# 04_DDRAM.net
KiCad netlist of a schematic drawn in Altium Designer
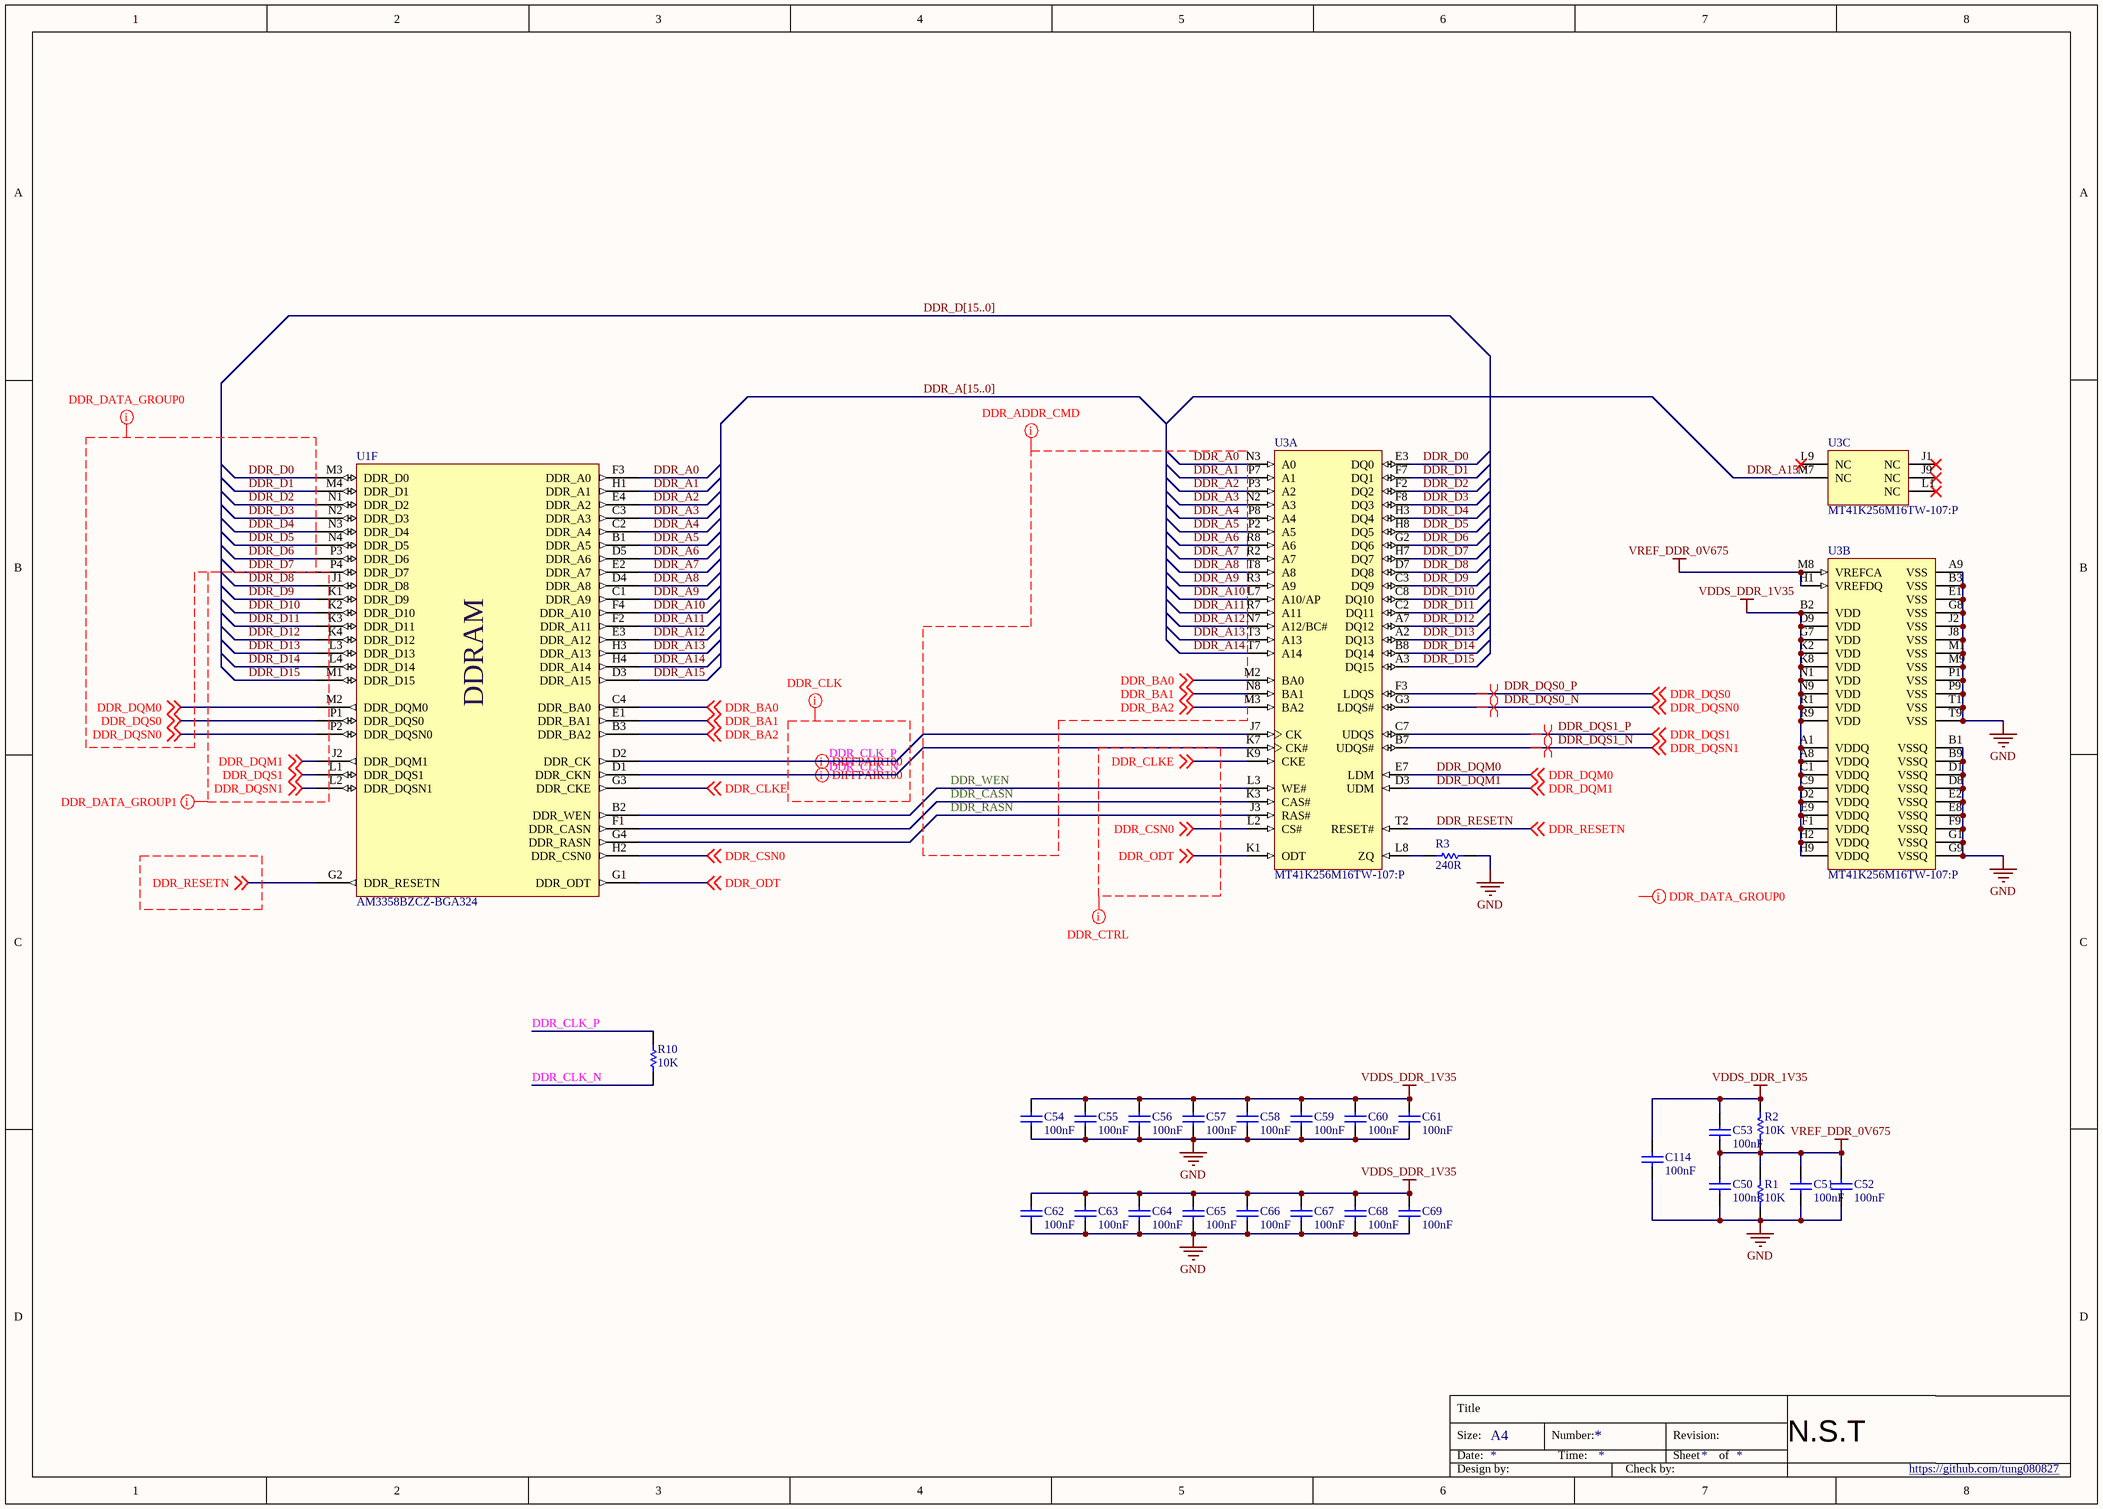
[diagram p0: 04. DDRAM.SchDoc]

(export (version "E")
  (design (tool "Eeschema 10.0.6"))
  (components
    (comp (ref "C50")
      (value "100nF")
      (footprint "CAPC1005X60X30LL05T10")
      (description "Chip Capacitor, 0.1 uF, +/- 10%, 16 V, -55 to 125 degC, 0402 (1005 Metric), RoHS, Tape and Reel")
      (fields (field (name "VOLTAGE") "16V") (field (name "TOLERANCE") "10%"))
      (libsource (lib "AM3358_DEV_BOARD") (part "CAP-NP-2"))
    )
    (comp (ref "C51")
      (value "100nF")
      (footprint "CAPC1005X60X30LL05T10")
      (description "Chip Capacitor, 0.1 uF, +/- 10%, 16 V, -55 to 125 degC, 0402 (1005 Metric), RoHS, Tape and Reel")
      (fields (field (name "VOLTAGE") "16V") (field (name "TOLERANCE") "10%"))
      (libsource (lib "AM3358_DEV_BOARD") (part "CAP-NP-2"))
    )
    (comp (ref "C52")
      (value "100nF")
      (footprint "CAPC1005X60X30LL05T10")
      (description "Chip Capacitor, 0.1 uF, +/- 10%, 16 V, -55 to 125 degC, 0402 (1005 Metric), RoHS, Tape and Reel")
      (fields (field (name "VOLTAGE") "16V") (field (name "TOLERANCE") "10%"))
      (libsource (lib "AM3358_DEV_BOARD") (part "CAP-NP-2"))
    )
    (comp (ref "C53")
      (value "100nF")
      (footprint "CAPC1005X60X30LL05T10")
      (description "Chip Capacitor, 0.1 uF, +/- 10%, 16 V, -55 to 125 degC, 0402 (1005 Metric), RoHS, Tape and Reel")
      (fields (field (name "VOLTAGE") "16V") (field (name "TOLERANCE") "10%"))
      (libsource (lib "AM3358_DEV_BOARD") (part "CAP-NP-2"))
    )
    (comp (ref "C54")
      (value "100nF")
      (footprint "CAPC1005X60X30LL05T10")
      (description "Chip Capacitor, 0.1 uF, +/- 10%, 16 V, -55 to 125 degC, 0402 (1005 Metric), RoHS, Tape and Reel")
      (fields (field (name "VOLTAGE") "16V") (field (name "TOLERANCE") "10%"))
      (libsource (lib "AM3358_DEV_BOARD") (part "CAP-NP-2"))
    )
    (comp (ref "C55")
      (value "100nF")
      (footprint "CAPC1005X60X30LL05T10")
      (description "Chip Capacitor, 0.1 uF, +/- 10%, 16 V, -55 to 125 degC, 0402 (1005 Metric), RoHS, Tape and Reel")
      (fields (field (name "VOLTAGE") "16V") (field (name "TOLERANCE") "10%"))
      (libsource (lib "AM3358_DEV_BOARD") (part "CAP-NP-2"))
    )
    (comp (ref "C56")
      (value "100nF")
      (footprint "CAPC1005X60X30LL05T10")
      (description "Chip Capacitor, 0.1 uF, +/- 10%, 16 V, -55 to 125 degC, 0402 (1005 Metric), RoHS, Tape and Reel")
      (fields (field (name "VOLTAGE") "16V") (field (name "TOLERANCE") "10%"))
      (libsource (lib "AM3358_DEV_BOARD") (part "CAP-NP-2"))
    )
    (comp (ref "C57")
      (value "100nF")
      (footprint "CAPC1005X60X30LL05T10")
      (description "Chip Capacitor, 0.1 uF, +/- 10%, 16 V, -55 to 125 degC, 0402 (1005 Metric), RoHS, Tape and Reel")
      (fields (field (name "VOLTAGE") "16V") (field (name "TOLERANCE") "10%"))
      (libsource (lib "AM3358_DEV_BOARD") (part "CAP-NP-2"))
    )
    (comp (ref "C58")
      (value "100nF")
      (footprint "CAPC1005X60X30LL05T10")
      (description "Chip Capacitor, 0.1 uF, +/- 10%, 16 V, -55 to 125 degC, 0402 (1005 Metric), RoHS, Tape and Reel")
      (fields (field (name "VOLTAGE") "16V") (field (name "TOLERANCE") "10%"))
      (libsource (lib "AM3358_DEV_BOARD") (part "CAP-NP-2"))
    )
    (comp (ref "C59")
      (value "100nF")
      (footprint "CAPC1005X60X30LL05T10")
      (description "Chip Capacitor, 0.1 uF, +/- 10%, 16 V, -55 to 125 degC, 0402 (1005 Metric), RoHS, Tape and Reel")
      (fields (field (name "VOLTAGE") "16V") (field (name "TOLERANCE") "10%"))
      (libsource (lib "AM3358_DEV_BOARD") (part "CAP-NP-2"))
    )
    (comp (ref "C60")
      (value "100nF")
      (footprint "CAPC1005X60X30LL05T10")
      (description "Chip Capacitor, 0.1 uF, +/- 10%, 16 V, -55 to 125 degC, 0402 (1005 Metric), RoHS, Tape and Reel")
      (fields (field (name "VOLTAGE") "16V") (field (name "TOLERANCE") "10%"))
      (libsource (lib "AM3358_DEV_BOARD") (part "CAP-NP-2"))
    )
    (comp (ref "C61")
      (value "100nF")
      (footprint "CAPC1005X60X30LL05T10")
      (description "Chip Capacitor, 0.1 uF, +/- 10%, 16 V, -55 to 125 degC, 0402 (1005 Metric), RoHS, Tape and Reel")
      (fields (field (name "VOLTAGE") "16V") (field (name "TOLERANCE") "10%"))
      (libsource (lib "AM3358_DEV_BOARD") (part "CAP-NP-2"))
    )
    (comp (ref "C62")
      (value "100nF")
      (footprint "CAPC1005X60X30LL05T10")
      (description "Chip Capacitor, 0.1 uF, +/- 10%, 16 V, -55 to 125 degC, 0402 (1005 Metric), RoHS, Tape and Reel")
      (fields (field (name "VOLTAGE") "16V") (field (name "TOLERANCE") "10%"))
      (libsource (lib "AM3358_DEV_BOARD") (part "CAP-NP-2"))
    )
    (comp (ref "C63")
      (value "100nF")
      (footprint "CAPC1005X60X30LL05T10")
      (description "Chip Capacitor, 0.1 uF, +/- 10%, 16 V, -55 to 125 degC, 0402 (1005 Metric), RoHS, Tape and Reel")
      (fields (field (name "VOLTAGE") "16V") (field (name "TOLERANCE") "10%"))
      (libsource (lib "AM3358_DEV_BOARD") (part "CAP-NP-2"))
    )
    (comp (ref "C64")
      (value "100nF")
      (footprint "CAPC1005X60X30LL05T10")
      (description "Chip Capacitor, 0.1 uF, +/- 10%, 16 V, -55 to 125 degC, 0402 (1005 Metric), RoHS, Tape and Reel")
      (fields (field (name "VOLTAGE") "16V") (field (name "TOLERANCE") "10%"))
      (libsource (lib "AM3358_DEV_BOARD") (part "CAP-NP-2"))
    )
    (comp (ref "C65")
      (value "100nF")
      (footprint "CAPC1005X60X30LL05T10")
      (description "Chip Capacitor, 0.1 uF, +/- 10%, 16 V, -55 to 125 degC, 0402 (1005 Metric), RoHS, Tape and Reel")
      (fields (field (name "VOLTAGE") "16V") (field (name "TOLERANCE") "10%"))
      (libsource (lib "AM3358_DEV_BOARD") (part "CAP-NP-2"))
    )
    (comp (ref "C66")
      (value "100nF")
      (footprint "CAPC1005X60X30LL05T10")
      (description "Chip Capacitor, 0.1 uF, +/- 10%, 16 V, -55 to 125 degC, 0402 (1005 Metric), RoHS, Tape and Reel")
      (fields (field (name "VOLTAGE") "16V") (field (name "TOLERANCE") "10%"))
      (libsource (lib "AM3358_DEV_BOARD") (part "CAP-NP-2"))
    )
    (comp (ref "C67")
      (value "100nF")
      (footprint "CAPC1005X60X30LL05T10")
      (description "Chip Capacitor, 0.1 uF, +/- 10%, 16 V, -55 to 125 degC, 0402 (1005 Metric), RoHS, Tape and Reel")
      (fields (field (name "VOLTAGE") "16V") (field (name "TOLERANCE") "10%"))
      (libsource (lib "AM3358_DEV_BOARD") (part "CAP-NP-2"))
    )
    (comp (ref "C68")
      (value "100nF")
      (footprint "CAPC1005X60X30LL05T10")
      (description "Chip Capacitor, 0.1 uF, +/- 10%, 16 V, -55 to 125 degC, 0402 (1005 Metric), RoHS, Tape and Reel")
      (fields (field (name "VOLTAGE") "16V") (field (name "TOLERANCE") "10%"))
      (libsource (lib "AM3358_DEV_BOARD") (part "CAP-NP-2"))
    )
    (comp (ref "C69")
      (value "100nF")
      (footprint "CAPC1005X60X30LL05T10")
      (description "Chip Capacitor, 0.1 uF, +/- 10%, 16 V, -55 to 125 degC, 0402 (1005 Metric), RoHS, Tape and Reel")
      (fields (field (name "VOLTAGE") "16V") (field (name "TOLERANCE") "10%"))
      (libsource (lib "AM3358_DEV_BOARD") (part "CAP-NP-2"))
    )
    (comp (ref "C114")
      (value "100nF")
      (footprint "CAPC1005X60X30LL05T10")
      (description "Chip Capacitor, 0.1 uF, +/- 10%, 16 V, -55 to 125 degC, 0402 (1005 Metric), RoHS, Tape and Reel")
      (fields (field (name "VOLTAGE") "16V") (field (name "TOLERANCE") "10%"))
      (libsource (lib "AM3358_DEV_BOARD") (part "CAP-NP-2"))
    )
    (comp (ref "R1")
      (value "10K")
      (footprint "RESC1005X40X25LL05T05")
      (description "SMD Resistor 1K Ohm 1/16W, 1%, 0402")
      (fields (field (name "MANUFACTURER") "Vishay Dale") (field (name "PART NUMBER") "CRCW0402240RFKED"))
      (libsource (lib "Altium Content Vault") (part "RES"))
    )
    (comp (ref "R2")
      (value "10K")
      (footprint "RESC1005X40X25LL05T05")
      (description "SMD Resistor 1K Ohm 1/16W, 1%, 0402")
      (fields (field (name "MANUFACTURER") "Vishay Dale") (field (name "PART NUMBER") "CRCW0402240RFKED"))
      (libsource (lib "Altium Content Vault") (part "RES"))
    )
    (comp (ref "R3")
      (value "240R")
      (footprint "RESC1005X40X25LL05T05")
      (description "SMD Resistor 240 Ohm 1/16W, 1%, 0402")
      (fields (field (name "MANUFACTURER") "Vishay Dale") (field (name "PART NUMBER") "CRCW0402240RFKED"))
      (libsource (lib "AM3358_DEV_BOARD") (part "RES"))
    )
    (comp (ref "R10")
      (value "10K")
      (footprint "RESC1005X40X25ML05T05")
      (description "SMD Resistor 1K Ohm 1/16W, 1%, 0402")
      (fields (field (name "MANUFACTURER") "Vishay Dale") (field (name "PART NUMBER") "CRCW0402240RFKED"))
      (libsource (lib "Altium Content Vault") (part "RES"))
    )
    (comp (ref "U1")
      (value "AM3358BZCZ-BGA324")
      (footprint "TI-ZCZ324")
      (libsource (lib "SyTungNguyen") (part "AM3358BZCZ100"))
    )
    (comp (ref "U3")
      (value "MT41K256M16TW-107:P")
      (footprint "MICT-TW-96")
      (description "DDR3L SDRAM, 4 GB, 933 MHz, 1.283 to 1.45 V, 0 to 95 degC, 96-Pin FBGA, RoHS, Tray")
      (fields (field (name "MANUFACTURER") "Micron"))
      (libsource (lib "") (part "MICT-MT41K256M16-TW-96_1"))
    )
  )
  (nets
    (net (code "1") (name "/DDR_A0") (class "Default")
      (node (ref "U1") (pin "F3") (pinfunction "DDR_A0_F3") (pintype "output"))
      (node (ref "U3") (pin "N3") (pinfunction "A0_N3") (pintype "input"))
    )
    (net (code "2") (name "/DDR_A1") (class "Default")
      (node (ref "U1") (pin "H1") (pinfunction "DDR_A1_H1") (pintype "output"))
      (node (ref "U3") (pin "P7") (pinfunction "A1_P7") (pintype "input"))
    )
    (net (code "3") (name "/DDR_A2") (class "Default")
      (node (ref "U1") (pin "E4") (pinfunction "DDR_A2_E4") (pintype "output"))
      (node (ref "U3") (pin "P3") (pinfunction "A2_P3") (pintype "input"))
    )
    (net (code "4") (name "/DDR_A3") (class "Default")
      (node (ref "U1") (pin "C3") (pinfunction "DDR_A3_C3") (pintype "output"))
      (node (ref "U3") (pin "N2") (pinfunction "A3_N2") (pintype "input"))
    )
    (net (code "5") (name "/DDR_A4") (class "Default")
      (node (ref "U1") (pin "C2") (pinfunction "DDR_A4_C2") (pintype "output"))
      (node (ref "U3") (pin "P8") (pinfunction "A4_P8") (pintype "input"))
    )
    (net (code "6") (name "/DDR_A5") (class "Default")
      (node (ref "U1") (pin "B1") (pinfunction "DDR_A5_B1") (pintype "output"))
      (node (ref "U3") (pin "P2") (pinfunction "A5_P2") (pintype "input"))
    )
    (net (code "7") (name "/DDR_A6") (class "Default")
      (node (ref "U1") (pin "D5") (pinfunction "DDR_A6_D5") (pintype "output"))
      (node (ref "U3") (pin "R8") (pinfunction "A6_R8") (pintype "input"))
    )
    (net (code "8") (name "/DDR_A7") (class "Default")
      (node (ref "U1") (pin "E2") (pinfunction "DDR_A7_E2") (pintype "output"))
      (node (ref "U3") (pin "R2") (pinfunction "A7_R2") (pintype "input"))
    )
    (net (code "9") (name "/DDR_A8") (class "Default")
      (node (ref "U1") (pin "D4") (pinfunction "DDR_A8_D4") (pintype "output"))
      (node (ref "U3") (pin "T8") (pinfunction "A8_T8") (pintype "input"))
    )
    (net (code "10") (name "/DDR_A9") (class "Default")
      (node (ref "U1") (pin "C1") (pinfunction "DDR_A9_C1") (pintype "output"))
      (node (ref "U3") (pin "R3") (pinfunction "A9_R3") (pintype "input"))
    )
    (net (code "11") (name "/DDR_A10") (class "Default")
      (node (ref "U1") (pin "F4") (pinfunction "DDR_A10_F4") (pintype "output"))
      (node (ref "U3") (pin "L7") (pinfunction "A10/AP_L7") (pintype "input"))
    )
    (net (code "12") (name "/DDR_A11") (class "Default")
      (node (ref "U1") (pin "F2") (pinfunction "DDR_A11_F2") (pintype "output"))
      (node (ref "U3") (pin "R7") (pinfunction "A11_R7") (pintype "input"))
    )
    (net (code "13") (name "/DDR_A12") (class "Default")
      (node (ref "U1") (pin "E3") (pinfunction "DDR_A12_E3") (pintype "output"))
      (node (ref "U3") (pin "N7") (pinfunction "A12/BC#_N7") (pintype "input"))
    )
    (net (code "14") (name "/DDR_A13") (class "Default")
      (node (ref "U1") (pin "H3") (pinfunction "DDR_A13_H3") (pintype "output"))
      (node (ref "U3") (pin "T3") (pinfunction "A13_T3") (pintype "input"))
    )
    (net (code "15") (name "/DDR_A14") (class "Default")
      (node (ref "U1") (pin "H4") (pinfunction "DDR_A14_H4") (pintype "output"))
      (node (ref "U3") (pin "T7") (pinfunction "A14_T7") (pintype "input"))
    )
    (net (code "16") (name "/DDR_A15") (class "Default")
      (node (ref "U1") (pin "D3") (pinfunction "DDR_A15_D3") (pintype "output"))
      (node (ref "U3") (pin "M7") (pinfunction "NC_M7") (pintype "passive"))
    )
    (net (code "18") (name "/DDR_CASN") (class "Default")
      (node (ref "U1") (pin "F1") (pinfunction "DDR_CASN_F1") (pintype "output"))
      (node (ref "U3") (pin "K3") (pinfunction "CAS#_K3") (pintype "input"))
    )
    (net (code "19") (name "/DDR_CLK_N") (class "Default")
      (node (ref "R10") (pin "2") (pinfunction "2_2") (pintype "passive"))
      (node (ref "U1") (pin "D1") (pinfunction "DDR_CKN_D1") (pintype "output"))
      (node (ref "U3") (pin "K7") (pinfunction "CK#_K7") (pintype "input"))
    )
    (net (code "20") (name "/DDR_CLK_P") (class "Default")
      (node (ref "R10") (pin "1") (pinfunction "1_1") (pintype "passive"))
      (node (ref "U1") (pin "D2") (pinfunction "DDR_CK_D2") (pintype "output"))
      (node (ref "U3") (pin "J7") (pinfunction "CK_J7") (pintype "input"))
    )
    (net (code "21") (name "/DDR_D0") (class "Default")
      (node (ref "U1") (pin "M3") (pinfunction "DDR_D0_M3") (pintype "bidirectional"))
      (node (ref "U3") (pin "E3") (pinfunction "DQ0_E3") (pintype "bidirectional"))
    )
    (net (code "22") (name "/DDR_D1") (class "Default")
      (node (ref "U1") (pin "M4") (pinfunction "DDR_D1_M4") (pintype "bidirectional"))
      (node (ref "U3") (pin "F7") (pinfunction "DQ1_F7") (pintype "bidirectional"))
    )
    (net (code "23") (name "/DDR_D2") (class "Default")
      (node (ref "U1") (pin "N1") (pinfunction "DDR_D2_N1") (pintype "bidirectional"))
      (node (ref "U3") (pin "F2") (pinfunction "DQ2_F2") (pintype "bidirectional"))
    )
    (net (code "24") (name "/DDR_D3") (class "Default")
      (node (ref "U1") (pin "N2") (pinfunction "DDR_D3_N2") (pintype "bidirectional"))
      (node (ref "U3") (pin "F8") (pinfunction "DQ3_F8") (pintype "bidirectional"))
    )
    (net (code "25") (name "/DDR_D4") (class "Default")
      (node (ref "U1") (pin "N3") (pinfunction "DDR_D4_N3") (pintype "bidirectional"))
      (node (ref "U3") (pin "H3") (pinfunction "DQ4_H3") (pintype "bidirectional"))
    )
    (net (code "26") (name "/DDR_D5") (class "Default")
      (node (ref "U1") (pin "N4") (pinfunction "DDR_D5_N4") (pintype "bidirectional"))
      (node (ref "U3") (pin "H8") (pinfunction "DQ5_H8") (pintype "bidirectional"))
    )
    (net (code "27") (name "/DDR_D6") (class "Default")
      (node (ref "U1") (pin "P3") (pinfunction "DDR_D6_P3") (pintype "bidirectional"))
      (node (ref "U3") (pin "G2") (pinfunction "DQ6_G2") (pintype "bidirectional"))
    )
    (net (code "28") (name "/DDR_D7") (class "Default")
      (node (ref "U1") (pin "P4") (pinfunction "DDR_D7_P4") (pintype "bidirectional"))
      (node (ref "U3") (pin "H7") (pinfunction "DQ7_H7") (pintype "bidirectional"))
    )
    (net (code "29") (name "/DDR_D8") (class "Default")
      (node (ref "U1") (pin "J1") (pinfunction "DDR_D8_J1") (pintype "bidirectional"))
      (node (ref "U3") (pin "D7") (pinfunction "DQ8_D7") (pintype "bidirectional"))
    )
    (net (code "30") (name "/DDR_D9") (class "Default")
      (node (ref "U1") (pin "K1") (pinfunction "DDR_D9_K1") (pintype "bidirectional"))
      (node (ref "U3") (pin "C3") (pinfunction "DQ9_C3") (pintype "bidirectional"))
    )
    (net (code "31") (name "/DDR_D10") (class "Default")
      (node (ref "U1") (pin "K2") (pinfunction "DDR_D10_K2") (pintype "bidirectional"))
      (node (ref "U3") (pin "C8") (pinfunction "DQ10_C8") (pintype "bidirectional"))
    )
    (net (code "32") (name "/DDR_D11") (class "Default")
      (node (ref "U1") (pin "K3") (pinfunction "DDR_D11_K3") (pintype "bidirectional"))
      (node (ref "U3") (pin "C2") (pinfunction "DQ11_C2") (pintype "bidirectional"))
    )
    (net (code "33") (name "/DDR_D12") (class "Default")
      (node (ref "U1") (pin "K4") (pinfunction "DDR_D12_K4") (pintype "bidirectional"))
      (node (ref "U3") (pin "A7") (pinfunction "DQ12_A7") (pintype "bidirectional"))
    )
    (net (code "34") (name "/DDR_D13") (class "Default")
      (node (ref "U1") (pin "L3") (pinfunction "DDR_D13_L3") (pintype "bidirectional"))
      (node (ref "U3") (pin "A2") (pinfunction "DQ13_A2") (pintype "bidirectional"))
    )
    (net (code "35") (name "/DDR_D14") (class "Default")
      (node (ref "U1") (pin "L4") (pinfunction "DDR_D14_L4") (pintype "bidirectional"))
      (node (ref "U3") (pin "B8") (pinfunction "DQ14_B8") (pintype "bidirectional"))
    )
    (net (code "36") (name "/DDR_D15") (class "Default")
      (node (ref "U1") (pin "M1") (pinfunction "DDR_D15_M1") (pintype "bidirectional"))
      (node (ref "U3") (pin "A3") (pinfunction "DQ15_A3") (pintype "bidirectional"))
    )
    (net (code "38") (name "/DDR_RASN") (class "Default")
      (node (ref "U1") (pin "G4") (pinfunction "DDR_RASN_G4") (pintype "output"))
      (node (ref "U3") (pin "J3") (pinfunction "RAS#_J3") (pintype "input"))
    )
    (net (code "39") (name "/DDR_WEN") (class "Default")
      (node (ref "U1") (pin "B2") (pinfunction "DDR_WEN_B2") (pintype "output"))
      (node (ref "U3") (pin "L3") (pinfunction "WE#_L3") (pintype "input"))
    )
    (net (code "40") (name "DDR_BA0") (class "Default")
      (node (ref "U1") (pin "C4") (pinfunction "DDR_BA0_C4") (pintype "output"))
      (node (ref "U3") (pin "M2") (pinfunction "BA0_M2") (pintype "input"))
    )
    (net (code "41") (name "DDR_BA1") (class "Default")
      (node (ref "U1") (pin "E1") (pinfunction "DDR_BA1_E1") (pintype "output"))
      (node (ref "U3") (pin "N8") (pinfunction "BA1_N8") (pintype "input"))
    )
    (net (code "42") (name "DDR_BA2") (class "Default")
      (node (ref "U1") (pin "B3") (pinfunction "DDR_BA2_B3") (pintype "output"))
      (node (ref "U3") (pin "M3") (pinfunction "BA2_M3") (pintype "input"))
    )
    (net (code "43") (name "DDR_CLKE") (class "Default")
      (node (ref "U1") (pin "G3") (pinfunction "DDR_CKE_G3") (pintype "output"))
      (node (ref "U3") (pin "K9") (pinfunction "CKE_K9") (pintype "input"))
    )
    (net (code "44") (name "DDR_CSN0") (class "Default")
      (node (ref "U1") (pin "H2") (pinfunction "DDR_CSN0_H2") (pintype "output"))
      (node (ref "U3") (pin "L2") (pinfunction "CS#_L2") (pintype "input"))
    )
    (net (code "45") (name "DDR_DQM0") (class "Default")
      (node (ref "U1") (pin "M2") (pinfunction "DDR_DQM0_M2") (pintype "output"))
      (node (ref "U3") (pin "E7") (pinfunction "LDM_E7") (pintype "input"))
    )
    (net (code "46") (name "DDR_DQM1") (class "Default")
      (node (ref "U1") (pin "J2") (pinfunction "DDR_DQM1_J2") (pintype "output"))
      (node (ref "U3") (pin "D3") (pinfunction "UDM_D3") (pintype "input"))
    )
    (net (code "47") (name "DDR_DQS0") (class "Default")
      (node (ref "U1") (pin "P1") (pinfunction "DDR_DQS0_P1") (pintype "bidirectional"))
      (node (ref "U3") (pin "F3") (pinfunction "LDQS_F3") (pintype "bidirectional"))
    )
    (net (code "48") (name "DDR_DQS1") (class "Default")
      (node (ref "U1") (pin "L1") (pinfunction "DDR_DQS1_L1") (pintype "bidirectional"))
      (node (ref "U3") (pin "C7") (pinfunction "UDQS_C7") (pintype "bidirectional"))
    )
    (net (code "49") (name "DDR_DQSN0") (class "Default")
      (node (ref "U1") (pin "P2") (pinfunction "DDR_DQSN0_P2") (pintype "bidirectional"))
      (node (ref "U3") (pin "G3") (pinfunction "LDQS#_G3") (pintype "bidirectional"))
    )
    (net (code "50") (name "DDR_DQSN1") (class "Default")
      (node (ref "U1") (pin "L2") (pinfunction "DDR_DQSN1_L2") (pintype "bidirectional"))
      (node (ref "U3") (pin "B7") (pinfunction "UDQS#_B7") (pintype "bidirectional"))
    )
    (net (code "51") (name "DDR_ODT") (class "Default")
      (node (ref "U1") (pin "G1") (pinfunction "DDR_ODT_G1") (pintype "output"))
      (node (ref "U3") (pin "K1") (pinfunction "ODT_K1") (pintype "input"))
    )
    (net (code "52") (name "DDR_RESETN") (class "Default")
      (node (ref "U1") (pin "G2") (pinfunction "DDR_RESETN_G2") (pintype "output"))
      (node (ref "U3") (pin "T2") (pinfunction "RESET#_T2") (pintype "input"))
    )
    (net (code "53") (name "GND") (class "Default")
      (node (ref "C114") (pin "1") (pinfunction "1_1") (pintype "passive"))
      (node (ref "C50") (pin "1") (pinfunction "1_1") (pintype "passive"))
      (node (ref "C51") (pin "1") (pinfunction "1_1") (pintype "passive"))
      (node (ref "C52") (pin "1") (pinfunction "1_1") (pintype "passive"))
      (node (ref "C54") (pin "1") (pinfunction "1_1") (pintype "passive"))
      (node (ref "C55") (pin "1") (pinfunction "1_1") (pintype "passive"))
      (node (ref "C56") (pin "1") (pinfunction "1_1") (pintype "passive"))
      (node (ref "C57") (pin "1") (pinfunction "1_1") (pintype "passive"))
      (node (ref "C58") (pin "1") (pinfunction "1_1") (pintype "passive"))
      (node (ref "C59") (pin "1") (pinfunction "1_1") (pintype "passive"))
      (node (ref "C60") (pin "1") (pinfunction "1_1") (pintype "passive"))
      (node (ref "C61") (pin "1") (pinfunction "1_1") (pintype "passive"))
      (node (ref "C62") (pin "1") (pinfunction "1_1") (pintype "passive"))
      (node (ref "C63") (pin "1") (pinfunction "1_1") (pintype "passive"))
      (node (ref "C64") (pin "1") (pinfunction "1_1") (pintype "passive"))
      (node (ref "C65") (pin "1") (pinfunction "1_1") (pintype "passive"))
      (node (ref "C66") (pin "1") (pinfunction "1_1") (pintype "passive"))
      (node (ref "C67") (pin "1") (pinfunction "1_1") (pintype "passive"))
      (node (ref "C68") (pin "1") (pinfunction "1_1") (pintype "passive"))
      (node (ref "C69") (pin "1") (pinfunction "1_1") (pintype "passive"))
      (node (ref "R1") (pin "1") (pinfunction "1_1") (pintype "passive"))
      (node (ref "R3") (pin "2") (pinfunction "2_2") (pintype "passive"))
      (node (ref "U3") (pin "A9") (pinfunction "VSS_A9") (pintype "power_in"))
      (node (ref "U3") (pin "B1") (pinfunction "VSSQ_B1") (pintype "power_in"))
      (node (ref "U3") (pin "B3") (pinfunction "VSS_B3") (pintype "power_in"))
      (node (ref "U3") (pin "B9") (pinfunction "VSSQ_B9") (pintype "power_in"))
      (node (ref "U3") (pin "D1") (pinfunction "VSSQ_D1") (pintype "power_in"))
      (node (ref "U3") (pin "D8") (pinfunction "VSSQ_D8") (pintype "power_in"))
      (node (ref "U3") (pin "E1") (pinfunction "VSS_E1") (pintype "power_in"))
      (node (ref "U3") (pin "E2") (pinfunction "VSSQ_E2") (pintype "power_in"))
      (node (ref "U3") (pin "E8") (pinfunction "VSSQ_E8") (pintype "power_in"))
      (node (ref "U3") (pin "F9") (pinfunction "VSSQ_F9") (pintype "power_in"))
      (node (ref "U3") (pin "G1") (pinfunction "VSSQ_G1") (pintype "power_in"))
      (node (ref "U3") (pin "G8") (pinfunction "VSS_G8") (pintype "power_in"))
      (node (ref "U3") (pin "G9") (pinfunction "VSSQ_G9") (pintype "power_in"))
      (node (ref "U3") (pin "J2") (pinfunction "VSS_J2") (pintype "power_in"))
      (node (ref "U3") (pin "J8") (pinfunction "VSS_J8") (pintype "power_in"))
      (node (ref "U3") (pin "M1") (pinfunction "VSS_M1") (pintype "power_in"))
      (node (ref "U3") (pin "M9") (pinfunction "VSS_M9") (pintype "power_in"))
      (node (ref "U3") (pin "P1") (pinfunction "VSS_P1") (pintype "power_in"))
      (node (ref "U3") (pin "P9") (pinfunction "VSS_P9") (pintype "power_in"))
      (node (ref "U3") (pin "T1") (pinfunction "VSS_T1") (pintype "power_in"))
      (node (ref "U3") (pin "T9") (pinfunction "VSS_T9") (pintype "power_in"))
    )
    (net (code "54") (name "Net-(U3A-ZQ)") (class "Default")
      (node (ref "R3") (pin "1") (pinfunction "1_1") (pintype "passive"))
      (node (ref "U3") (pin "L8") (pinfunction "ZQ_L8") (pintype "input"))
    )
    (net (code "55") (name "VDDS_DDR_1V35") (class "Default")
      (node (ref "C114") (pin "2") (pinfunction "2_2") (pintype "passive"))
      (node (ref "C53") (pin "2") (pinfunction "2_2") (pintype "passive"))
      (node (ref "C54") (pin "2") (pinfunction "2_2") (pintype "passive"))
      (node (ref "C55") (pin "2") (pinfunction "2_2") (pintype "passive"))
      (node (ref "C56") (pin "2") (pinfunction "2_2") (pintype "passive"))
      (node (ref "C57") (pin "2") (pinfunction "2_2") (pintype "passive"))
      (node (ref "C58") (pin "2") (pinfunction "2_2") (pintype "passive"))
      (node (ref "C59") (pin "2") (pinfunction "2_2") (pintype "passive"))
      (node (ref "C60") (pin "2") (pinfunction "2_2") (pintype "passive"))
      (node (ref "C61") (pin "2") (pinfunction "2_2") (pintype "passive"))
      (node (ref "C62") (pin "2") (pinfunction "2_2") (pintype "passive"))
      (node (ref "C63") (pin "2") (pinfunction "2_2") (pintype "passive"))
      (node (ref "C64") (pin "2") (pinfunction "2_2") (pintype "passive"))
      (node (ref "C65") (pin "2") (pinfunction "2_2") (pintype "passive"))
      (node (ref "C66") (pin "2") (pinfunction "2_2") (pintype "passive"))
      (node (ref "C67") (pin "2") (pinfunction "2_2") (pintype "passive"))
      (node (ref "C68") (pin "2") (pinfunction "2_2") (pintype "passive"))
      (node (ref "C69") (pin "2") (pinfunction "2_2") (pintype "passive"))
      (node (ref "R2") (pin "2") (pinfunction "2_2") (pintype "passive"))
      (node (ref "U3") (pin "A1") (pinfunction "VDDQ_A1") (pintype "power_in"))
      (node (ref "U3") (pin "A8") (pinfunction "VDDQ_A8") (pintype "power_in"))
      (node (ref "U3") (pin "B2") (pinfunction "VDD_B2") (pintype "power_in"))
      (node (ref "U3") (pin "C1") (pinfunction "VDDQ_C1") (pintype "power_in"))
      (node (ref "U3") (pin "C9") (pinfunction "VDDQ_C9") (pintype "power_in"))
      (node (ref "U3") (pin "D2") (pinfunction "VDDQ_D2") (pintype "power_in"))
      (node (ref "U3") (pin "D9") (pinfunction "VDD_D9") (pintype "power_in"))
      (node (ref "U3") (pin "E9") (pinfunction "VDDQ_E9") (pintype "power_in"))
      (node (ref "U3") (pin "F1") (pinfunction "VDDQ_F1") (pintype "power_in"))
      (node (ref "U3") (pin "G7") (pinfunction "VDD_G7") (pintype "power_in"))
      (node (ref "U3") (pin "H2") (pinfunction "VDDQ_H2") (pintype "power_in"))
      (node (ref "U3") (pin "H9") (pinfunction "VDDQ_H9") (pintype "power_in"))
      (node (ref "U3") (pin "K2") (pinfunction "VDD_K2") (pintype "power_in"))
      (node (ref "U3") (pin "K8") (pinfunction "VDD_K8") (pintype "power_in"))
      (node (ref "U3") (pin "N1") (pinfunction "VDD_N1") (pintype "power_in"))
      (node (ref "U3") (pin "N9") (pinfunction "VDD_N9") (pintype "power_in"))
      (node (ref "U3") (pin "R1") (pinfunction "VDD_R1") (pintype "power_in"))
      (node (ref "U3") (pin "R9") (pinfunction "VDD_R9") (pintype "power_in"))
    )
    (net (code "56") (name "VREF_DDR_0V675") (class "Default")
      (node (ref "C50") (pin "2") (pinfunction "2_2") (pintype "passive"))
      (node (ref "C51") (pin "2") (pinfunction "2_2") (pintype "passive"))
      (node (ref "C52") (pin "2") (pinfunction "2_2") (pintype "passive"))
      (node (ref "C53") (pin "1") (pinfunction "1_1") (pintype "passive"))
      (node (ref "R1") (pin "2") (pinfunction "2_2") (pintype "passive"))
      (node (ref "R2") (pin "1") (pinfunction "1_1") (pintype "passive"))
      (node (ref "U3") (pin "H1") (pinfunction "VREFDQ_H1") (pintype "input"))
      (node (ref "U3") (pin "M8") (pinfunction "VREFCA_M8") (pintype "input"))
    )
    (net (code "57") (name "unconnected-(U3C-NC-PadJ1)") (class "Default")
      (node (ref "U3") (pin "J1") (pinfunction "NC_J1") (pintype "passive+no_connect"))
    )
    (net (code "58") (name "unconnected-(U3C-NC-PadJ9)") (class "Default")
      (node (ref "U3") (pin "J9") (pinfunction "NC_J9") (pintype "passive+no_connect"))
    )
    (net (code "59") (name "unconnected-(U3C-NC-PadL1)") (class "Default")
      (node (ref "U3") (pin "L1") (pinfunction "NC_L1") (pintype "passive+no_connect"))
    )
    (net (code "60") (name "unconnected-(U3C-NC-PadL9)") (class "Default")
      (node (ref "U3") (pin "L9") (pinfunction "NC_L9") (pintype "passive+no_connect"))
    )
  )
)
